# SFP__Connectors.net
KiCad netlist of a schematic drawn in Altium Designer
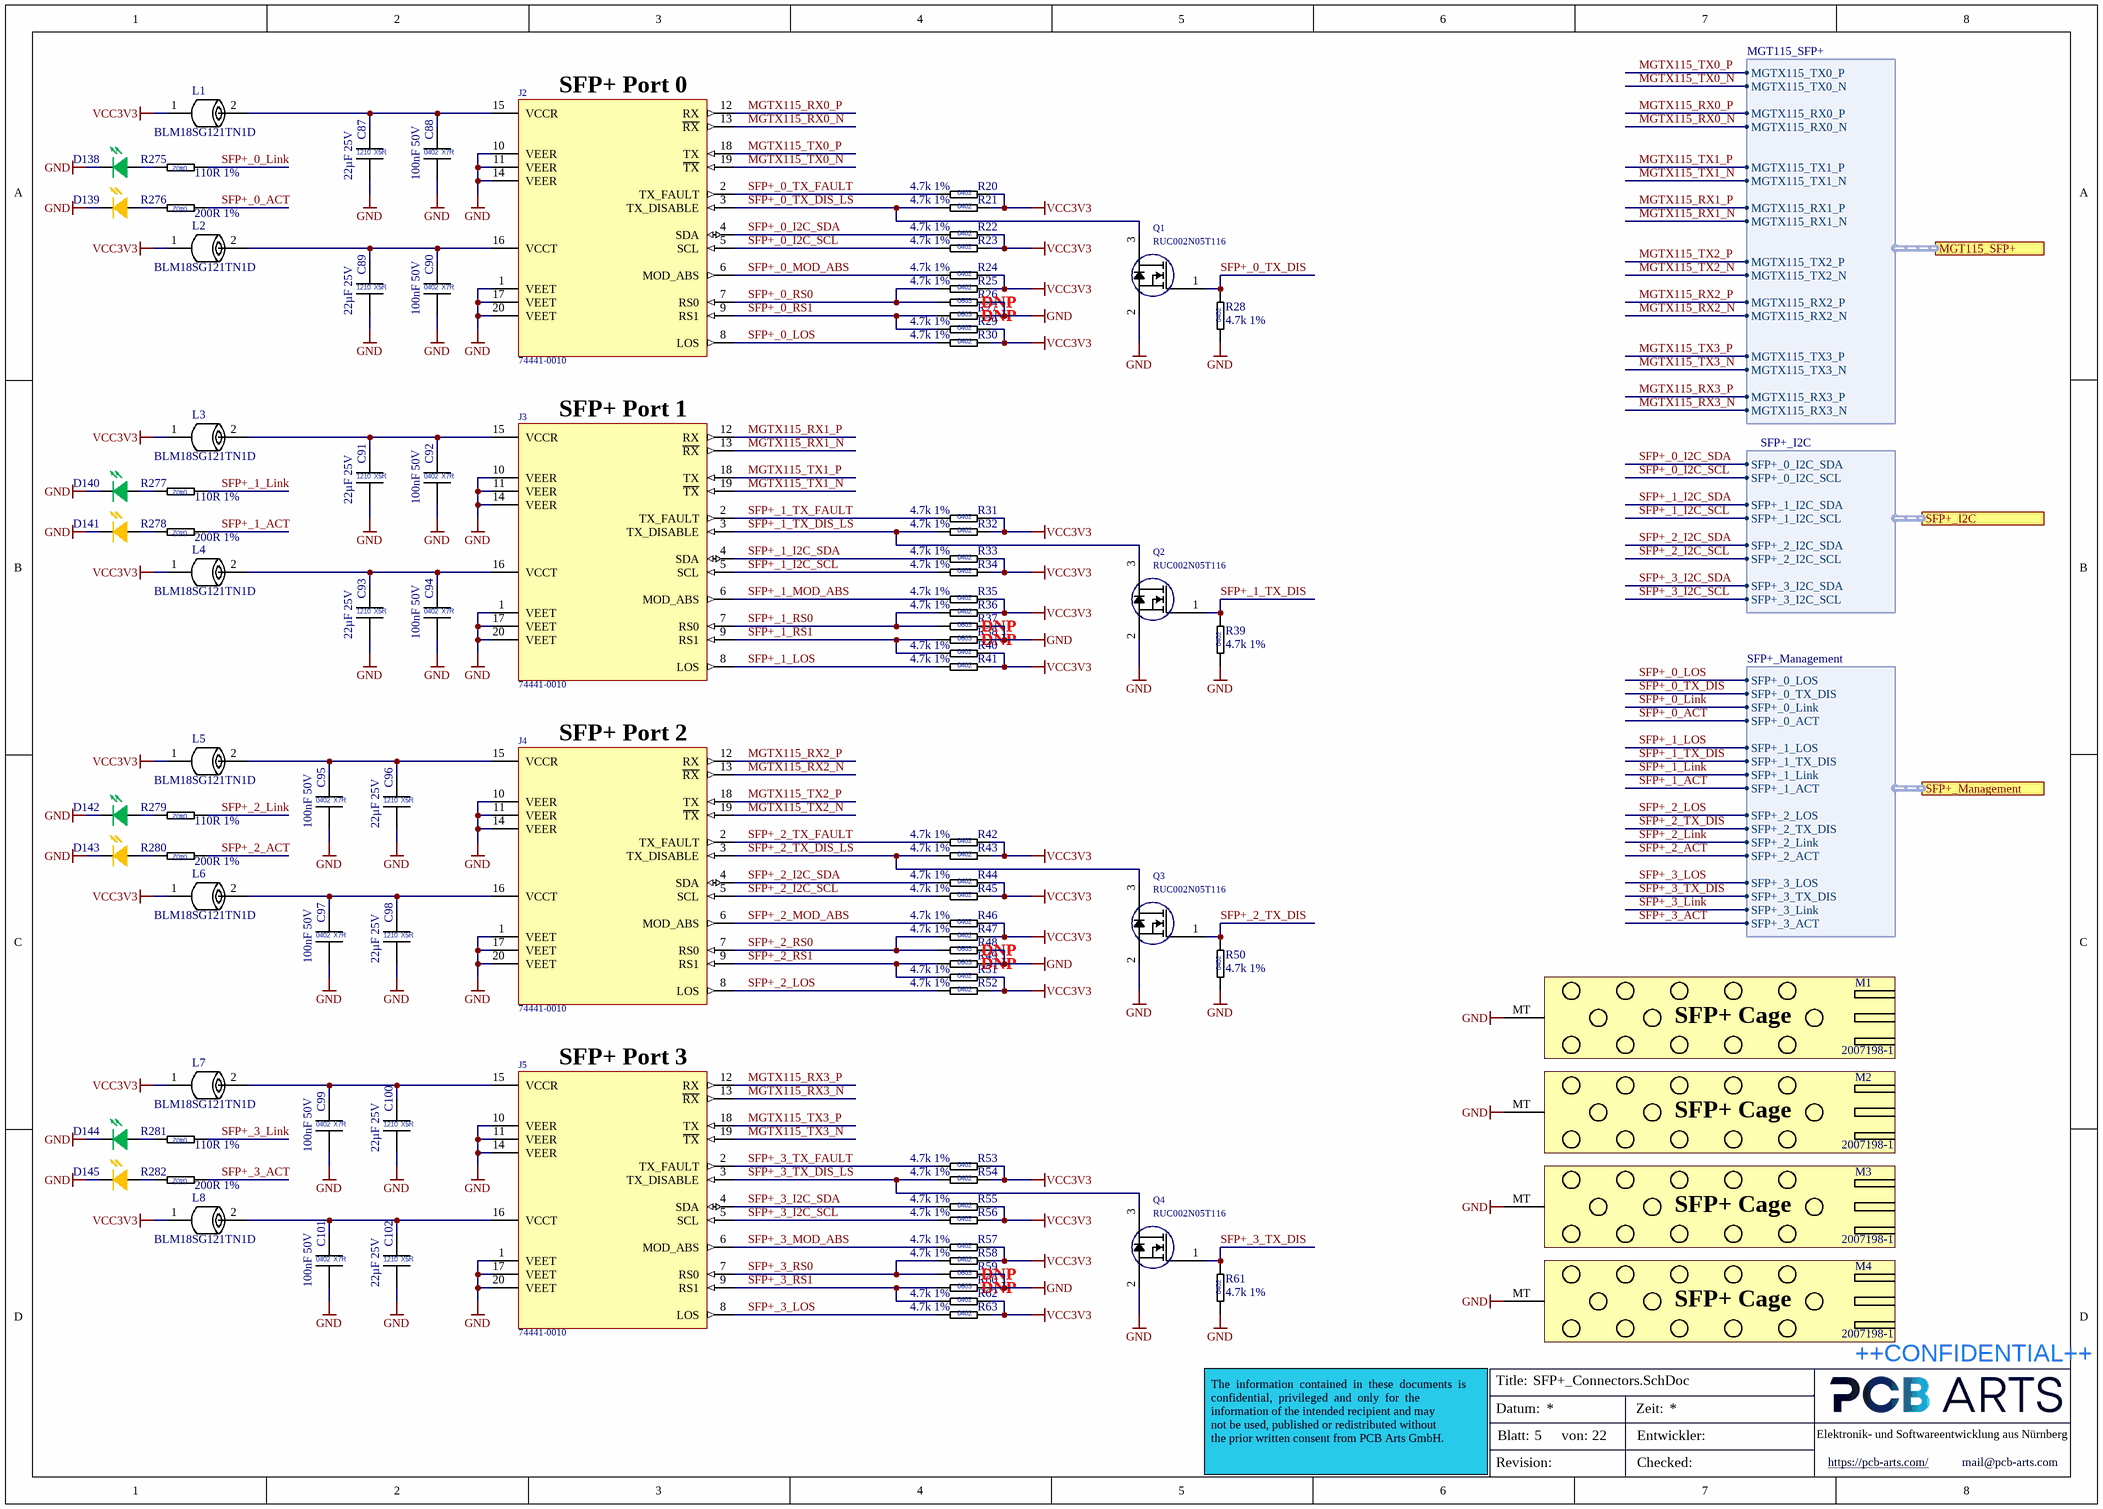
[diagram p0: SFP+_Connectors.SchDoc]

(export (version "E")
  (design (tool "Eeschema 10.0.6"))
  (components
    (comp (ref "C87")
      (value "22µF 25V")
      (footprint "Cap:CAP_1210")
      (description "Multilayer Ceramic Capacitors MLCC - SMD/SMT 1210 25VDC")
      (libsource (lib "Cap") (part "CAP_1210_22µF_25V"))
    )
    (comp (ref "C88")
      (value "100nF 50V")
      (footprint "Cap:CAP_0402_L")
      (description "Multilayer Ceramic Capacitors MLCC - SMD/SMT 0402 50VDC")
      (libsource (lib "Cap") (part "CAP_0402_100nF_50V"))
    )
    (comp (ref "C89")
      (value "22µF 25V")
      (footprint "Cap:CAP_1210")
      (description "Multilayer Ceramic Capacitors MLCC - SMD/SMT 1210 25VDC")
      (libsource (lib "Cap") (part "CAP_1210_22µF_25V"))
    )
    (comp (ref "C90")
      (value "100nF 50V")
      (footprint "Cap:CAP_0402_L")
      (description "Multilayer Ceramic Capacitors MLCC - SMD/SMT 0402 50VDC")
      (libsource (lib "Cap") (part "CAP_0402_100nF_50V"))
    )
    (comp (ref "C91")
      (value "22µF 25V")
      (footprint "Cap:CAP_1210")
      (description "Multilayer Ceramic Capacitors MLCC - SMD/SMT 1210 25VDC")
      (libsource (lib "Cap") (part "CAP_1210_22µF_25V"))
    )
    (comp (ref "C92")
      (value "100nF 50V")
      (footprint "Cap:CAP_0402_L")
      (description "Multilayer Ceramic Capacitors MLCC - SMD/SMT 0402 50VDC")
      (libsource (lib "Cap") (part "CAP_0402_100nF_50V"))
    )
    (comp (ref "C93")
      (value "22µF 25V")
      (footprint "Cap:CAP_1210")
      (description "Multilayer Ceramic Capacitors MLCC - SMD/SMT 1210 25VDC")
      (libsource (lib "Cap") (part "CAP_1210_22µF_25V"))
    )
    (comp (ref "C94")
      (value "100nF 50V")
      (footprint "Cap:CAP_0402_L")
      (description "Multilayer Ceramic Capacitors MLCC - SMD/SMT 0402 50VDC")
      (libsource (lib "Cap") (part "CAP_0402_100nF_50V"))
    )
    (comp (ref "C95")
      (value "100nF 50V")
      (footprint "Cap:CAP_0402_L")
      (description "Multilayer Ceramic Capacitors MLCC - SMD/SMT 0402 50VDC")
      (libsource (lib "Cap") (part "CAP_0402_100nF_50V"))
    )
    (comp (ref "C96")
      (value "22µF 25V")
      (footprint "Cap:CAP_1210")
      (description "Multilayer Ceramic Capacitors MLCC - SMD/SMT 1210 25VDC")
      (libsource (lib "Cap") (part "CAP_1210_22µF_25V"))
    )
    (comp (ref "C97")
      (value "100nF 50V")
      (footprint "Cap:CAP_0402_L")
      (description "Multilayer Ceramic Capacitors MLCC - SMD/SMT 0402 50VDC")
      (libsource (lib "Cap") (part "CAP_0402_100nF_50V"))
    )
    (comp (ref "C98")
      (value "22µF 25V")
      (footprint "Cap:CAP_1210")
      (description "Multilayer Ceramic Capacitors MLCC - SMD/SMT 1210 25VDC")
      (libsource (lib "Cap") (part "CAP_1210_22µF_25V"))
    )
    (comp (ref "C99")
      (value "100nF 50V")
      (footprint "Cap:CAP_0402_L")
      (description "Multilayer Ceramic Capacitors MLCC - SMD/SMT 0402 50VDC")
      (libsource (lib "Cap") (part "CAP_0402_100nF_50V"))
    )
    (comp (ref "C100")
      (value "22µF 25V")
      (footprint "Cap:CAP_1210")
      (description "Multilayer Ceramic Capacitors MLCC - SMD/SMT 1210 25VDC")
      (libsource (lib "Cap") (part "CAP_1210_22µF_25V"))
    )
    (comp (ref "C101")
      (value "100nF 50V")
      (footprint "Cap:CAP_0402_L")
      (description "Multilayer Ceramic Capacitors MLCC - SMD/SMT 0402 50VDC")
      (libsource (lib "Cap") (part "CAP_0402_100nF_50V"))
    )
    (comp (ref "C102")
      (value "22µF 25V")
      (footprint "Cap:CAP_1210")
      (description "Multilayer Ceramic Capacitors MLCC - SMD/SMT 1210 25VDC")
      (libsource (lib "Cap") (part "CAP_1210_22µF_25V"))
    )
    (comp (ref "D138")
      (value "LTST-S270KGKT")
      (footprint "Active:LED-0603 Sideview")
      (description "GREEN  0603 Light Emitting Diode")
      (libsource (lib "Active") (part "LED 0603 Green Sideview"))
    )
    (comp (ref "D139")
      (value "LTST-S270KFKT")
      (footprint "Active:LED-0603 Sideview")
      (description "ORANGE 0603 Light Emitting Diode")
      (libsource (lib "Active") (part "LED 0603 ORANGE Sideview"))
    )
    (comp (ref "D140")
      (value "LTST-S270KGKT")
      (footprint "Active:LED-0603 Sideview")
      (description "GREEN  0603 Light Emitting Diode")
      (libsource (lib "Active") (part "LED 0603 Green Sideview"))
    )
    (comp (ref "D141")
      (value "LTST-S270KFKT")
      (footprint "Active:LED-0603 Sideview")
      (description "ORANGE 0603 Light Emitting Diode")
      (libsource (lib "Active") (part "LED 0603 ORANGE Sideview"))
    )
    (comp (ref "D142")
      (value "LTST-S270KGKT")
      (footprint "Active:LED-0603 Sideview")
      (description "GREEN  0603 Light Emitting Diode")
      (libsource (lib "Active") (part "LED 0603 Green Sideview"))
    )
    (comp (ref "D143")
      (value "LTST-S270KFKT")
      (footprint "Active:LED-0603 Sideview")
      (description "ORANGE 0603 Light Emitting Diode")
      (libsource (lib "Active") (part "LED 0603 ORANGE Sideview"))
    )
    (comp (ref "D144")
      (value "LTST-S270KGKT")
      (footprint "Active:LED-0603 Sideview")
      (description "GREEN  0603 Light Emitting Diode")
      (libsource (lib "Active") (part "LED 0603 Green Sideview"))
    )
    (comp (ref "D145")
      (value "LTST-S270KFKT")
      (footprint "Active:LED-0603 Sideview")
      (description "ORANGE 0603 Light Emitting Diode")
      (libsource (lib "Active") (part "LED 0603 ORANGE Sideview"))
    )
    (comp (ref "J2")
      (value "74441-0010")
      (footprint "Conn:74441-0010")
      (description "20 Pin Right Angle 0.8mm SMD Card Edge Connector for SFP+")
      (libsource (lib "Conn") (part "74441-0010_Card Edge Connector for SFP+"))
    )
    (comp (ref "J3")
      (value "74441-0010")
      (footprint "Conn:74441-0010")
      (description "20 Pin Right Angle 0.8mm SMD Card Edge Connector for SFP+")
      (libsource (lib "Conn") (part "74441-0010_Card Edge Connector for SFP+"))
    )
    (comp (ref "J4")
      (value "74441-0010")
      (footprint "Conn:74441-0010")
      (description "20 Pin Right Angle 0.8mm SMD Card Edge Connector for SFP+")
      (libsource (lib "Conn") (part "74441-0010_Card Edge Connector for SFP+"))
    )
    (comp (ref "J5")
      (value "74441-0010")
      (footprint "Conn:74441-0010")
      (description "20 Pin Right Angle 0.8mm SMD Card Edge Connector for SFP+")
      (libsource (lib "Conn") (part "74441-0010_Card Edge Connector for SFP+"))
    )
    (comp (ref "L1")
      (value "BLM18SG121TN1D")
      (footprint "Indc:L_0603")
      (description "Ferritperlen BLM18_xN 0603 100MHz 120Ohm 3000mA 25mOhm RSER")
      (libsource (lib "Indc") (part "BLM18SG121TN1D_Ferrite Beads 0603 120Ohms 3000mA"))
    )
    (comp (ref "L2")
      (value "BLM18SG121TN1D")
      (footprint "Indc:L_0603")
      (description "Ferritperlen BLM18_xN 0603 100MHz 120Ohm 3000mA 25mOhm RSER")
      (libsource (lib "Indc") (part "BLM18SG121TN1D_Ferrite Beads 0603 120Ohms 3000mA"))
    )
    (comp (ref "L3")
      (value "BLM18SG121TN1D")
      (footprint "Indc:L_0603")
      (description "Ferritperlen BLM18_xN 0603 100MHz 120Ohm 3000mA 25mOhm RSER")
      (libsource (lib "Indc") (part "BLM18SG121TN1D_Ferrite Beads 0603 120Ohms 3000mA"))
    )
    (comp (ref "L4")
      (value "BLM18SG121TN1D")
      (footprint "Indc:L_0603")
      (description "Ferritperlen BLM18_xN 0603 100MHz 120Ohm 3000mA 25mOhm RSER")
      (libsource (lib "Indc") (part "BLM18SG121TN1D_Ferrite Beads 0603 120Ohms 3000mA"))
    )
    (comp (ref "L5")
      (value "BLM18SG121TN1D")
      (footprint "Indc:L_0603")
      (description "Ferritperlen BLM18_xN 0603 100MHz 120Ohm 3000mA 25mOhm RSER")
      (libsource (lib "Indc") (part "BLM18SG121TN1D_Ferrite Beads 0603 120Ohms 3000mA"))
    )
    (comp (ref "L6")
      (value "BLM18SG121TN1D")
      (footprint "Indc:L_0603")
      (description "Ferritperlen BLM18_xN 0603 100MHz 120Ohm 3000mA 25mOhm RSER")
      (libsource (lib "Indc") (part "BLM18SG121TN1D_Ferrite Beads 0603 120Ohms 3000mA"))
    )
    (comp (ref "L7")
      (value "BLM18SG121TN1D")
      (footprint "Indc:L_0603")
      (description "Ferritperlen BLM18_xN 0603 100MHz 120Ohm 3000mA 25mOhm RSER")
      (libsource (lib "Indc") (part "BLM18SG121TN1D_Ferrite Beads 0603 120Ohms 3000mA"))
    )
    (comp (ref "L8")
      (value "BLM18SG121TN1D")
      (footprint "Indc:L_0603")
      (description "Ferritperlen BLM18_xN 0603 100MHz 120Ohm 3000mA 25mOhm RSER")
      (libsource (lib "Indc") (part "BLM18SG121TN1D_Ferrite Beads 0603 120Ohms 3000mA"))
    )
    (comp (ref "M1")
      (value "2007198-1")
      (footprint "Conn:2007198-1")
      (description "2SFP+ Cage, 1x1, external EMV springs, no lightpipes")
      (libsource (lib "Conn") (part "2007198-1_2SFP+ Cage, 1x1, external EMV springs, no lightpipes"))
    )
    (comp (ref "M2")
      (value "2007198-1")
      (footprint "Conn:2007198-1")
      (description "2SFP+ Cage, 1x1, external EMV springs, no lightpipes")
      (libsource (lib "Conn") (part "2007198-1_2SFP+ Cage, 1x1, external EMV springs, no lightpipes"))
    )
    (comp (ref "M3")
      (value "2007198-1")
      (footprint "Conn:2007198-1")
      (description "2SFP+ Cage, 1x1, external EMV springs, no lightpipes")
      (libsource (lib "Conn") (part "2007198-1_2SFP+ Cage, 1x1, external EMV springs, no lightpipes"))
    )
    (comp (ref "M4")
      (value "2007198-1")
      (footprint "Conn:2007198-1")
      (description "2SFP+ Cage, 1x1, external EMV springs, no lightpipes")
      (libsource (lib "Conn") (part "2007198-1_2SFP+ Cage, 1x1, external EMV springs, no lightpipes"))
    )
    (comp (ref "Q1")
      (value "RUC002N05T116")
      (footprint "trans:SOT95P251X112-3N")
      (description "MOSFET N-Ch 1.2 VGS Spec")
      (libsource (lib "Trans") (part "RUC002N05T116_MOSFET N-Ch 1.2 VGS Spec"))
    )
    (comp (ref "Q2")
      (value "RUC002N05T116")
      (footprint "trans:SOT95P251X112-3N")
      (description "MOSFET N-Ch 1.2 VGS Spec")
      (libsource (lib "Trans") (part "RUC002N05T116_MOSFET N-Ch 1.2 VGS Spec"))
    )
    (comp (ref "Q3")
      (value "RUC002N05T116")
      (footprint "trans:SOT95P251X112-3N")
      (description "MOSFET N-Ch 1.2 VGS Spec")
      (libsource (lib "Trans") (part "RUC002N05T116_MOSFET N-Ch 1.2 VGS Spec"))
    )
    (comp (ref "Q4")
      (value "RUC002N05T116")
      (footprint "trans:SOT95P251X112-3N")
      (description "MOSFET N-Ch 1.2 VGS Spec")
      (libsource (lib "Trans") (part "RUC002N05T116_MOSFET N-Ch 1.2 VGS Spec"))
    )
    (comp (ref "R20")
      (value "4.7k 1%")
      (footprint "Res:RES_0402_L")
      (description "Thick Film Resistors - SMD 4.7kOhm 1%")
      (libsource (lib "Res") (part "RES_0402_4.7k_1%"))
    )
    (comp (ref "R21")
      (value "4.7k 1%")
      (footprint "Res:RES_0402_L")
      (description "Thick Film Resistors - SMD 4.7kOhm 1%")
      (libsource (lib "Res") (part "RES_0402_4.7k_1%"))
    )
    (comp (ref "R22")
      (value "4.7k 1%")
      (footprint "Res:RES_0402_L")
      (description "Thick Film Resistors - SMD 4.7kOhm 1%")
      (libsource (lib "Res") (part "RES_0402_4.7k_1%"))
    )
    (comp (ref "R23")
      (value "4.7k 1%")
      (footprint "Res:RES_0402_L")
      (description "Thick Film Resistors - SMD 4.7kOhm 1%")
      (libsource (lib "Res") (part "RES_0402_4.7k_1%"))
    )
    (comp (ref "R24")
      (value "4.7k 1%")
      (footprint "Res:RES_0402_L")
      (description "Thick Film Resistors - SMD 4.7kOhm 1%")
      (libsource (lib "Res") (part "RES_0402_4.7k_1%"))
    )
    (comp (ref "R25")
      (value "4.7k 1%")
      (footprint "Res:RES_0402_L")
      (description "Thick Film Resistors - SMD 4.7kOhm 1%")
      (libsource (lib "Res") (part "RES_0402_4.7k_1%"))
    )
    (comp (ref "R26")
      (value "0R Jumper")
      (footprint "Res:RES_0603_L")
      (description "Thick Film Resistors - SMD 0Ohm Jumper")
      (libsource (lib "Res") (part "RES_0603_0R_Jumper"))
    )
    (comp (ref "R27")
      (value "0R Jumper")
      (footprint "Res:RES_0603_L")
      (description "Thick Film Resistors - SMD 0Ohm Jumper")
      (libsource (lib "Res") (part "RES_0603_0R_Jumper"))
    )
    (comp (ref "R28")
      (value "4.7k 1%")
      (footprint "Res:RES_0402_L")
      (description "Thick Film Resistors - SMD 4.7kOhm 1%")
      (libsource (lib "Res") (part "RES_0402_4.7k_1%"))
    )
    (comp (ref "R29")
      (value "4.7k 1%")
      (footprint "Res:RES_0402_L")
      (description "Thick Film Resistors - SMD 4.7kOhm 1%")
      (libsource (lib "Res") (part "RES_0402_4.7k_1%"))
    )
    (comp (ref "R30")
      (value "4.7k 1%")
      (footprint "Res:RES_0402_L")
      (description "Thick Film Resistors - SMD 4.7kOhm 1%")
      (libsource (lib "Res") (part "RES_0402_4.7k_1%"))
    )
    (comp (ref "R31")
      (value "4.7k 1%")
      (footprint "Res:RES_0402_L")
      (description "Thick Film Resistors - SMD 4.7kOhm 1%")
      (libsource (lib "Res") (part "RES_0402_4.7k_1%"))
    )
    (comp (ref "R32")
      (value "4.7k 1%")
      (footprint "Res:RES_0402_L")
      (description "Thick Film Resistors - SMD 4.7kOhm 1%")
      (libsource (lib "Res") (part "RES_0402_4.7k_1%"))
    )
    (comp (ref "R33")
      (value "4.7k 1%")
      (footprint "Res:RES_0402_L")
      (description "Thick Film Resistors - SMD 4.7kOhm 1%")
      (libsource (lib "Res") (part "RES_0402_4.7k_1%"))
    )
    (comp (ref "R34")
      (value "4.7k 1%")
      (footprint "Res:RES_0402_L")
      (description "Thick Film Resistors - SMD 4.7kOhm 1%")
      (libsource (lib "Res") (part "RES_0402_4.7k_1%"))
    )
    (comp (ref "R35")
      (value "4.7k 1%")
      (footprint "Res:RES_0402_L")
      (description "Thick Film Resistors - SMD 4.7kOhm 1%")
      (libsource (lib "Res") (part "RES_0402_4.7k_1%"))
    )
    (comp (ref "R36")
      (value "4.7k 1%")
      (footprint "Res:RES_0402_L")
      (description "Thick Film Resistors - SMD 4.7kOhm 1%")
      (libsource (lib "Res") (part "RES_0402_4.7k_1%"))
    )
    (comp (ref "R37")
      (value "0R Jumper")
      (footprint "Res:RES_0603_L")
      (description "Thick Film Resistors - SMD 0Ohm Jumper")
      (libsource (lib "Res") (part "RES_0603_0R_Jumper"))
    )
    (comp (ref "R38")
      (value "0R Jumper")
      (footprint "Res:RES_0603_L")
      (description "Thick Film Resistors - SMD 0Ohm Jumper")
      (libsource (lib "Res") (part "RES_0603_0R_Jumper"))
    )
    (comp (ref "R39")
      (value "4.7k 1%")
      (footprint "Res:RES_0402_L")
      (description "Thick Film Resistors - SMD 4.7kOhm 1%")
      (libsource (lib "Res") (part "RES_0402_4.7k_1%"))
    )
    (comp (ref "R40")
      (value "4.7k 1%")
      (footprint "Res:RES_0402_L")
      (description "Thick Film Resistors - SMD 4.7kOhm 1%")
      (libsource (lib "Res") (part "RES_0402_4.7k_1%"))
    )
    (comp (ref "R41")
      (value "4.7k 1%")
      (footprint "Res:RES_0402_L")
      (description "Thick Film Resistors - SMD 4.7kOhm 1%")
      (libsource (lib "Res") (part "RES_0402_4.7k_1%"))
    )
    (comp (ref "R42")
      (value "4.7k 1%")
      (footprint "Res:RES_0402_L")
      (description "Thick Film Resistors - SMD 4.7kOhm 1%")
      (libsource (lib "Res") (part "RES_0402_4.7k_1%"))
    )
    (comp (ref "R43")
      (value "4.7k 1%")
      (footprint "Res:RES_0402_L")
      (description "Thick Film Resistors - SMD 4.7kOhm 1%")
      (libsource (lib "Res") (part "RES_0402_4.7k_1%"))
    )
    (comp (ref "R44")
      (value "4.7k 1%")
      (footprint "Res:RES_0402_L")
      (description "Thick Film Resistors - SMD 4.7kOhm 1%")
      (libsource (lib "Res") (part "RES_0402_4.7k_1%"))
    )
    (comp (ref "R45")
      (value "4.7k 1%")
      (footprint "Res:RES_0402_L")
      (description "Thick Film Resistors - SMD 4.7kOhm 1%")
      (libsource (lib "Res") (part "RES_0402_4.7k_1%"))
    )
    (comp (ref "R46")
      (value "4.7k 1%")
      (footprint "Res:RES_0402_L")
      (description "Thick Film Resistors - SMD 4.7kOhm 1%")
      (libsource (lib "Res") (part "RES_0402_4.7k_1%"))
    )
    (comp (ref "R47")
      (value "4.7k 1%")
      (footprint "Res:RES_0402_L")
      (description "Thick Film Resistors - SMD 4.7kOhm 1%")
      (libsource (lib "Res") (part "RES_0402_4.7k_1%"))
    )
    (comp (ref "R48")
      (value "0R Jumper")
      (footprint "Res:RES_0603_L")
      (description "Thick Film Resistors - SMD 0Ohm Jumper")
      (libsource (lib "Res") (part "RES_0603_0R_Jumper"))
    )
    (comp (ref "R49")
      (value "0R Jumper")
      (footprint "Res:RES_0603_L")
      (description "Thick Film Resistors - SMD 0Ohm Jumper")
      (libsource (lib "Res") (part "RES_0603_0R_Jumper"))
    )
    (comp (ref "R50")
      (value "4.7k 1%")
      (footprint "Res:RES_0402_L")
      (description "Thick Film Resistors - SMD 4.7kOhm 1%")
      (libsource (lib "Res") (part "RES_0402_4.7k_1%"))
    )
    (comp (ref "R51")
      (value "4.7k 1%")
      (footprint "Res:RES_0402_L")
      (description "Thick Film Resistors - SMD 4.7kOhm 1%")
      (libsource (lib "Res") (part "RES_0402_4.7k_1%"))
    )
    (comp (ref "R52")
      (value "4.7k 1%")
      (footprint "Res:RES_0402_L")
      (description "Thick Film Resistors - SMD 4.7kOhm 1%")
      (libsource (lib "Res") (part "RES_0402_4.7k_1%"))
    )
    (comp (ref "R53")
      (value "4.7k 1%")
      (footprint "Res:RES_0402_L")
      (description "Thick Film Resistors - SMD 4.7kOhm 1%")
      (libsource (lib "Res") (part "RES_0402_4.7k_1%"))
    )
    (comp (ref "R54")
      (value "4.7k 1%")
      (footprint "Res:RES_0402_L")
      (description "Thick Film Resistors - SMD 4.7kOhm 1%")
      (libsource (lib "Res") (part "RES_0402_4.7k_1%"))
    )
    (comp (ref "R55")
      (value "4.7k 1%")
      (footprint "Res:RES_0402_L")
      (description "Thick Film Resistors - SMD 4.7kOhm 1%")
      (libsource (lib "Res") (part "RES_0402_4.7k_1%"))
    )
    (comp (ref "R56")
      (value "4.7k 1%")
      (footprint "Res:RES_0402_L")
      (description "Thick Film Resistors - SMD 4.7kOhm 1%")
      (libsource (lib "Res") (part "RES_0402_4.7k_1%"))
    )
    (comp (ref "R57")
      (value "4.7k 1%")
      (footprint "Res:RES_0402_L")
      (description "Thick Film Resistors - SMD 4.7kOhm 1%")
      (libsource (lib "Res") (part "RES_0402_4.7k_1%"))
    )
    (comp (ref "R58")
      (value "4.7k 1%")
      (footprint "Res:RES_0402_L")
      (description "Thick Film Resistors - SMD 4.7kOhm 1%")
      (libsource (lib "Res") (part "RES_0402_4.7k_1%"))
    )
    (comp (ref "R59")
      (value "0R Jumper")
      (footprint "Res:RES_0603_L")
      (description "Thick Film Resistors - SMD 0Ohm Jumper")
      (libsource (lib "Res") (part "RES_0603_0R_Jumper"))
    )
    (comp (ref "R60")
      (value "0R Jumper")
      (footprint "Res:RES_0603_L")
      (description "Thick Film Resistors - SMD 0Ohm Jumper")
      (libsource (lib "Res") (part "RES_0603_0R_Jumper"))
    )
    (comp (ref "R61")
      (value "4.7k 1%")
      (footprint "Res:RES_0402_L")
      (description "Thick Film Resistors - SMD 4.7kOhm 1%")
      (libsource (lib "Res") (part "RES_0402_4.7k_1%"))
    )
    (comp (ref "R62")
      (value "4.7k 1%")
      (footprint "Res:RES_0402_L")
      (description "Thick Film Resistors - SMD 4.7kOhm 1%")
      (libsource (lib "Res") (part "RES_0402_4.7k_1%"))
    )
    (comp (ref "R63")
      (value "4.7k 1%")
      (footprint "Res:RES_0402_L")
      (description "Thick Film Resistors - SMD 4.7kOhm 1%")
      (libsource (lib "Res") (part "RES_0402_4.7k_1%"))
    )
    (comp (ref "R275")
      (value "110R 1%")
      (footprint "Res:RES_0402_L")
      (description "Thick Film Resistors - SMD 110Ohm 1%")
      (libsource (lib "Res") (part "RES_0402_110R_1%"))
    )
    (comp (ref "R276")
      (value "200R 1%")
      (footprint "Res:RES_0402_L")
      (description "Thick Film Resistors - SMD 200Ohm 1%")
      (libsource (lib "Res") (part "RES_0402_200R 1%"))
    )
    (comp (ref "R277")
      (value "110R 1%")
      (footprint "Res:RES_0402_L")
      (description "Thick Film Resistors - SMD 110Ohm 1%")
      (libsource (lib "Res") (part "RES_0402_110R_1%"))
    )
    (comp (ref "R278")
      (value "200R 1%")
      (footprint "Res:RES_0402_L")
      (description "Thick Film Resistors - SMD 200Ohm 1%")
      (libsource (lib "Res") (part "RES_0402_200R 1%"))
    )
    (comp (ref "R279")
      (value "110R 1%")
      (footprint "Res:RES_0402_L")
      (description "Thick Film Resistors - SMD 110Ohm 1%")
      (libsource (lib "Res") (part "RES_0402_110R_1%"))
    )
    (comp (ref "R280")
      (value "200R 1%")
      (footprint "Res:RES_0402_L")
      (description "Thick Film Resistors - SMD 200Ohm 1%")
      (libsource (lib "Res") (part "RES_0402_200R 1%"))
    )
    (comp (ref "R281")
      (value "110R 1%")
      (footprint "Res:RES_0402_L")
      (description "Thick Film Resistors - SMD 110Ohm 1%")
      (libsource (lib "Res") (part "RES_0402_110R_1%"))
    )
    (comp (ref "R282")
      (value "200R 1%")
      (footprint "Res:RES_0402_L")
      (description "Thick Film Resistors - SMD 200Ohm 1%")
      (libsource (lib "Res") (part "RES_0402_200R 1%"))
    )
  )
  (nets
    (net (code "4") (name "/MGTX115_RX0_N") (class "Default")
      (node (ref "J2") (pin "13") (pinfunction "~{RX}_13") (pintype "output"))
    )
    (net (code "5") (name "/MGTX115_RX0_P") (class "Default")
      (node (ref "J2") (pin "12") (pinfunction "RX_12") (pintype "output"))
    )
    (net (code "6") (name "/MGTX115_RX1_N") (class "Default")
      (node (ref "J3") (pin "13") (pinfunction "~{RX}_13") (pintype "output"))
    )
    (net (code "7") (name "/MGTX115_RX1_P") (class "Default")
      (node (ref "J3") (pin "12") (pinfunction "RX_12") (pintype "output"))
    )
    (net (code "8") (name "/MGTX115_RX2_N") (class "Default")
      (node (ref "J4") (pin "13") (pinfunction "~{RX}_13") (pintype "output"))
    )
    (net (code "9") (name "/MGTX115_RX2_P") (class "Default")
      (node (ref "J4") (pin "12") (pinfunction "RX_12") (pintype "output"))
    )
    (net (code "10") (name "/MGTX115_RX3_N") (class "Default")
      (node (ref "J5") (pin "13") (pinfunction "~{RX}_13") (pintype "output"))
    )
    (net (code "11") (name "/MGTX115_RX3_P") (class "Default")
      (node (ref "J5") (pin "12") (pinfunction "RX_12") (pintype "output"))
    )
    (net (code "12") (name "/MGTX115_TX0_N") (class "Default")
      (node (ref "J2") (pin "19") (pinfunction "~{TX}_19") (pintype "input"))
    )
    (net (code "13") (name "/MGTX115_TX0_P") (class "Default")
      (node (ref "J2") (pin "18") (pinfunction "TX_18") (pintype "input"))
    )
    (net (code "14") (name "/MGTX115_TX1_N") (class "Default")
      (node (ref "J3") (pin "19") (pinfunction "~{TX}_19") (pintype "input"))
    )
    (net (code "15") (name "/MGTX115_TX1_P") (class "Default")
      (node (ref "J3") (pin "18") (pinfunction "TX_18") (pintype "input"))
    )
    (net (code "16") (name "/MGTX115_TX2_N") (class "Default")
      (node (ref "J4") (pin "19") (pinfunction "~{TX}_19") (pintype "input"))
    )
    (net (code "17") (name "/MGTX115_TX2_P") (class "Default")
      (node (ref "J4") (pin "18") (pinfunction "TX_18") (pintype "input"))
    )
    (net (code "18") (name "/MGTX115_TX3_N") (class "Default")
      (node (ref "J5") (pin "19") (pinfunction "~{TX}_19") (pintype "input"))
    )
    (net (code "19") (name "/MGTX115_TX3_P") (class "Default")
      (node (ref "J5") (pin "18") (pinfunction "TX_18") (pintype "input"))
    )
    (net (code "20") (name "/SFP+_0_ACT") (class "Default")
      (node (ref "R276") (pin "1") (pinfunction "1_1") (pintype "passive"))
    )
    (net (code "21") (name "/SFP+_0_I2C_SCL") (class "Default")
      (node (ref "J2") (pin "5") (pinfunction "SCL_5") (pintype "input"))
      (node (ref "R23") (pin "1") (pinfunction "1_1") (pintype "passive"))
    )
    (net (code "22") (name "/SFP+_0_I2C_SDA") (class "Default")
      (node (ref "J2") (pin "4") (pinfunction "SDA_4") (pintype "bidirectional"))
      (node (ref "R22") (pin "1") (pinfunction "1_1") (pintype "passive"))
    )
    (net (code "23") (name "/SFP+_0_LOS") (class "Default")
      (node (ref "J2") (pin "8") (pinfunction "LOS_8") (pintype "output"))
      (node (ref "R30") (pin "1") (pinfunction "1_1") (pintype "passive"))
    )
    (net (code "24") (name "/SFP+_0_Link") (class "Default")
      (node (ref "R275") (pin "1") (pinfunction "1_1") (pintype "passive"))
    )
    (net (code "25") (name "/SFP+_0_MOD_ABS") (class "Default")
      (node (ref "J2") (pin "6") (pinfunction "MOD_ABS_6") (pintype "output"))
      (node (ref "R24") (pin "1") (pinfunction "1_1") (pintype "passive"))
    )
    (net (code "26") (name "/SFP+_0_RS0") (class "Default")
      (node (ref "J2") (pin "7") (pinfunction "RS0_7") (pintype "input"))
      (node (ref "R25") (pin "1") (pinfunction "1_1") (pintype "passive"))
      (node (ref "R26") (pin "1") (pinfunction "1_1") (pintype "passive"))
    )
    (net (code "27") (name "/SFP+_0_RS1") (class "Default")
      (node (ref "J2") (pin "9") (pinfunction "RS1_9") (pintype "input"))
      (node (ref "R27") (pin "1") (pinfunction "1_1") (pintype "passive"))
      (node (ref "R29") (pin "1") (pinfunction "1_1") (pintype "passive"))
    )
    (net (code "28") (name "/SFP+_0_TX_DIS") (class "Default")
      (node (ref "Q1") (pin "1") (pinfunction "G_1") (pintype "passive"))
      (node (ref "R28") (pin "2") (pinfunction "2_2") (pintype "passive"))
    )
    (net (code "29") (name "/SFP+_0_TX_DIS_LS") (class "Default")
      (node (ref "J2") (pin "3") (pinfunction "TX_DISABLE_3") (pintype "input"))
      (node (ref "Q1") (pin "3") (pinfunction "S_3") (pintype "passive"))
      (node (ref "R21") (pin "1") (pinfunction "1_1") (pintype "passive"))
    )
    (net (code "30") (name "/SFP+_0_TX_FAULT") (class "Default")
      (node (ref "J2") (pin "2") (pinfunction "TX_FAULT_2") (pintype "output"))
      (node (ref "R20") (pin "1") (pinfunction "1_1") (pintype "passive"))
    )
    (net (code "31") (name "/SFP+_1_ACT") (class "Default")
      (node (ref "R278") (pin "1") (pinfunction "1_1") (pintype "passive"))
    )
    (net (code "32") (name "/SFP+_1_I2C_SCL") (class "Default")
      (node (ref "J3") (pin "5") (pinfunction "SCL_5") (pintype "input"))
      (node (ref "R34") (pin "1") (pinfunction "1_1") (pintype "passive"))
    )
    (net (code "33") (name "/SFP+_1_I2C_SDA") (class "Default")
      (node (ref "J3") (pin "4") (pinfunction "SDA_4") (pintype "bidirectional"))
      (node (ref "R33") (pin "1") (pinfunction "1_1") (pintype "passive"))
    )
    (net (code "34") (name "/SFP+_1_LOS") (class "Default")
      (node (ref "J3") (pin "8") (pinfunction "LOS_8") (pintype "output"))
      (node (ref "R41") (pin "1") (pinfunction "1_1") (pintype "passive"))
    )
    (net (code "35") (name "/SFP+_1_Link") (class "Default")
      (node (ref "R277") (pin "1") (pinfunction "1_1") (pintype "passive"))
    )
    (net (code "36") (name "/SFP+_1_MOD_ABS") (class "Default")
      (node (ref "J3") (pin "6") (pinfunction "MOD_ABS_6") (pintype "output"))
      (node (ref "R35") (pin "1") (pinfunction "1_1") (pintype "passive"))
    )
    (net (code "37") (name "/SFP+_1_RS0") (class "Default")
      (node (ref "J3") (pin "7") (pinfunction "RS0_7") (pintype "input"))
      (node (ref "R36") (pin "1") (pinfunction "1_1") (pintype "passive"))
      (node (ref "R37") (pin "1") (pinfunction "1_1") (pintype "passive"))
    )
    (net (code "38") (name "/SFP+_1_RS1") (class "Default")
      (node (ref "J3") (pin "9") (pinfunction "RS1_9") (pintype "input"))
      (node (ref "R38") (pin "1") (pinfunction "1_1") (pintype "passive"))
      (node (ref "R40") (pin "1") (pinfunction "1_1") (pintype "passive"))
    )
    (net (code "39") (name "/SFP+_1_TX_DIS") (class "Default")
      (node (ref "Q2") (pin "1") (pinfunction "G_1") (pintype "passive"))
      (node (ref "R39") (pin "2") (pinfunction "2_2") (pintype "passive"))
    )
    (net (code "40") (name "/SFP+_1_TX_DIS_LS") (class "Default")
      (node (ref "J3") (pin "3") (pinfunction "TX_DISABLE_3") (pintype "input"))
      (node (ref "Q2") (pin "3") (pinfunction "S_3") (pintype "passive"))
      (node (ref "R32") (pin "1") (pinfunction "1_1") (pintype "passive"))
    )
    (net (code "41") (name "/SFP+_1_TX_FAULT") (class "Default")
      (node (ref "J3") (pin "2") (pinfunction "TX_FAULT_2") (pintype "output"))
      (node (ref "R31") (pin "1") (pinfunction "1_1") (pintype "passive"))
    )
    (net (code "42") (name "/SFP+_2_ACT") (class "Default")
      (node (ref "R280") (pin "1") (pinfunction "1_1") (pintype "passive"))
    )
    (net (code "43") (name "/SFP+_2_I2C_SCL") (class "Default")
      (node (ref "J4") (pin "5") (pinfunction "SCL_5") (pintype "input"))
      (node (ref "R45") (pin "1") (pinfunction "1_1") (pintype "passive"))
    )
    (net (code "44") (name "/SFP+_2_I2C_SDA") (class "Default")
      (node (ref "J4") (pin "4") (pinfunction "SDA_4") (pintype "bidirectional"))
      (node (ref "R44") (pin "1") (pinfunction "1_1") (pintype "passive"))
    )
    (net (code "45") (name "/SFP+_2_LOS") (class "Default")
      (node (ref "J4") (pin "8") (pinfunction "LOS_8") (pintype "output"))
      (node (ref "R52") (pin "1") (pinfunction "1_1") (pintype "passive"))
    )
    (net (code "46") (name "/SFP+_2_Link") (class "Default")
      (node (ref "R279") (pin "1") (pinfunction "1_1") (pintype "passive"))
    )
    (net (code "47") (name "/SFP+_2_MOD_ABS") (class "Default")
      (node (ref "J4") (pin "6") (pinfunction "MOD_ABS_6") (pintype "output"))
      (node (ref "R46") (pin "1") (pinfunction "1_1") (pintype "passive"))
    )
    (net (code "48") (name "/SFP+_2_RS0") (class "Default")
      (node (ref "J4") (pin "7") (pinfunction "RS0_7") (pintype "input"))
      (node (ref "R47") (pin "1") (pinfunction "1_1") (pintype "passive"))
      (node (ref "R48") (pin "1") (pinfunction "1_1") (pintype "passive"))
    )
    (net (code "49") (name "/SFP+_2_RS1") (class "Default")
      (node (ref "J4") (pin "9") (pinfunction "RS1_9") (pintype "input"))
      (node (ref "R49") (pin "1") (pinfunction "1_1") (pintype "passive"))
      (node (ref "R51") (pin "1") (pinfunction "1_1") (pintype "passive"))
    )
    (net (code "50") (name "/SFP+_2_TX_DIS") (class "Default")
      (node (ref "Q3") (pin "1") (pinfunction "G_1") (pintype "passive"))
      (node (ref "R50") (pin "2") (pinfunction "2_2") (pintype "passive"))
    )
    (net (code "51") (name "/SFP+_2_TX_DIS_LS") (class "Default")
      (node (ref "J4") (pin "3") (pinfunction "TX_DISABLE_3") (pintype "input"))
      (node (ref "Q3") (pin "3") (pinfunction "S_3") (pintype "passive"))
      (node (ref "R43") (pin "1") (pinfunction "1_1") (pintype "passive"))
    )
    (net (code "52") (name "/SFP+_2_TX_FAULT") (class "Default")
      (node (ref "J4") (pin "2") (pinfunction "TX_FAULT_2") (pintype "output"))
      (node (ref "R42") (pin "1") (pinfunction "1_1") (pintype "passive"))
    )
    (net (code "53") (name "/SFP+_3_ACT") (class "Default")
      (node (ref "R282") (pin "1") (pinfunction "1_1") (pintype "passive"))
    )
    (net (code "54") (name "/SFP+_3_I2C_SCL") (class "Default")
      (node (ref "J5") (pin "5") (pinfunction "SCL_5") (pintype "input"))
      (node (ref "R56") (pin "1") (pinfunction "1_1") (pintype "passive"))
    )
    (net (code "55") (name "/SFP+_3_I2C_SDA") (class "Default")
      (node (ref "J5") (pin "4") (pinfunction "SDA_4") (pintype "bidirectional"))
      (node (ref "R55") (pin "1") (pinfunction "1_1") (pintype "passive"))
    )
    (net (code "56") (name "/SFP+_3_LOS") (class "Default")
      (node (ref "J5") (pin "8") (pinfunction "LOS_8") (pintype "output"))
      (node (ref "R63") (pin "1") (pinfunction "1_1") (pintype "passive"))
    )
    (net (code "57") (name "/SFP+_3_Link") (class "Default")
      (node (ref "R281") (pin "1") (pinfunction "1_1") (pintype "passive"))
    )
    (net (code "58") (name "/SFP+_3_MOD_ABS") (class "Default")
      (node (ref "J5") (pin "6") (pinfunction "MOD_ABS_6") (pintype "output"))
      (node (ref "R57") (pin "1") (pinfunction "1_1") (pintype "passive"))
    )
    (net (code "59") (name "/SFP+_3_RS0") (class "Default")
      (node (ref "J5") (pin "7") (pinfunction "RS0_7") (pintype "input"))
      (node (ref "R58") (pin "1") (pinfunction "1_1") (pintype "passive"))
      (node (ref "R59") (pin "1") (pinfunction "1_1") (pintype "passive"))
    )
    (net (code "60") (name "/SFP+_3_RS1") (class "Default")
      (node (ref "J5") (pin "9") (pinfunction "RS1_9") (pintype "input"))
      (node (ref "R60") (pin "1") (pinfunction "1_1") (pintype "passive"))
      (node (ref "R62") (pin "1") (pinfunction "1_1") (pintype "passive"))
    )
    (net (code "61") (name "/SFP+_3_TX_DIS") (class "Default")
      (node (ref "Q4") (pin "1") (pinfunction "G_1") (pintype "passive"))
      (node (ref "R61") (pin "2") (pinfunction "2_2") (pintype "passive"))
    )
    (net (code "62") (name "/SFP+_3_TX_DIS_LS") (class "Default")
      (node (ref "J5") (pin "3") (pinfunction "TX_DISABLE_3") (pintype "input"))
      (node (ref "Q4") (pin "3") (pinfunction "S_3") (pintype "passive"))
      (node (ref "R54") (pin "1") (pinfunction "1_1") (pintype "passive"))
    )
    (net (code "63") (name "/SFP+_3_TX_FAULT") (class "Default")
      (node (ref "J5") (pin "2") (pinfunction "TX_FAULT_2") (pintype "output"))
      (node (ref "R53") (pin "1") (pinfunction "1_1") (pintype "passive"))
    )
    (net (code "67") (name "GND") (class "Default")
      (node (ref "C100") (pin "2") (pinfunction "2_2") (pintype "passive"))
      (node (ref "C101") (pin "2") (pinfunction "2_2") (pintype "passive"))
      (node (ref "C102") (pin "2") (pinfunction "2_2") (pintype "passive"))
      (node (ref "C87") (pin "2") (pinfunction "2_2") (pintype "passive"))
      (node (ref "C88") (pin "2") (pinfunction "2_2") (pintype "passive"))
      (node (ref "C89") (pin "2") (pinfunction "2_2") (pintype "passive"))
      (node (ref "C90") (pin "2") (pinfunction "2_2") (pintype "passive"))
      (node (ref "C91") (pin "2") (pinfunction "2_2") (pintype "passive"))
      (node (ref "C92") (pin "2") (pinfunction "2_2") (pintype "passive"))
      (node (ref "C93") (pin "2") (pinfunction "2_2") (pintype "passive"))
      (node (ref "C94") (pin "2") (pinfunction "2_2") (pintype "passive"))
      (node (ref "C95") (pin "2") (pinfunction "2_2") (pintype "passive"))
      (node (ref "C96") (pin "2") (pinfunction "2_2") (pintype "passive"))
      (node (ref "C97") (pin "2") (pinfunction "2_2") (pintype "passive"))
      (node (ref "C98") (pin "2") (pinfunction "2_2") (pintype "passive"))
      (node (ref "C99") (pin "2") (pinfunction "2_2") (pintype "passive"))
      (node (ref "D138") (pin "1") (pinfunction "1_1") (pintype "passive"))
      (node (ref "D139") (pin "1") (pinfunction "1_1") (pintype "passive"))
      (node (ref "D140") (pin "1") (pinfunction "1_1") (pintype "passive"))
      (node (ref "D141") (pin "1") (pinfunction "1_1") (pintype "passive"))
      (node (ref "D142") (pin "1") (pinfunction "1_1") (pintype "passive"))
      (node (ref "D143") (pin "1") (pinfunction "1_1") (pintype "passive"))
      (node (ref "D144") (pin "1") (pinfunction "1_1") (pintype "passive"))
      (node (ref "D145") (pin "1") (pinfunction "1_1") (pintype "passive"))
      (node (ref "J2") (pin "1") (pinfunction "VEET_1") (pintype "power_in"))
      (node (ref "J2") (pin "10") (pinfunction "VEER_10") (pintype "power_in"))
      (node (ref "J2") (pin "11") (pinfunction "VEER_11") (pintype "power_in"))
      (node (ref "J2") (pin "14") (pinfunction "VEER_14") (pintype "power_in"))
      (node (ref "J2") (pin "17") (pinfunction "VEET_17") (pintype "power_in"))
      (node (ref "J2") (pin "20") (pinfunction "VEET_20") (pintype "power_in"))
      (node (ref "J3") (pin "1") (pinfunction "VEET_1") (pintype "power_in"))
      (node (ref "J3") (pin "10") (pinfunction "VEER_10") (pintype "power_in"))
      (node (ref "J3") (pin "11") (pinfunction "VEER_11") (pintype "power_in"))
      (node (ref "J3") (pin "14") (pinfunction "VEER_14") (pintype "power_in"))
      (node (ref "J3") (pin "17") (pinfunction "VEET_17") (pintype "power_in"))
      (node (ref "J3") (pin "20") (pinfunction "VEET_20") (pintype "power_in"))
      (node (ref "J4") (pin "1") (pinfunction "VEET_1") (pintype "power_in"))
      (node (ref "J4") (pin "10") (pinfunction "VEER_10") (pintype "power_in"))
      (node (ref "J4") (pin "11") (pinfunction "VEER_11") (pintype "power_in"))
      (node (ref "J4") (pin "14") (pinfunction "VEER_14") (pintype "power_in"))
      (node (ref "J4") (pin "17") (pinfunction "VEET_17") (pintype "power_in"))
      (node (ref "J4") (pin "20") (pinfunction "VEET_20") (pintype "power_in"))
      (node (ref "J5") (pin "1") (pinfunction "VEET_1") (pintype "power_in"))
      (node (ref "J5") (pin "10") (pinfunction "VEER_10") (pintype "power_in"))
      (node (ref "J5") (pin "11") (pinfunction "VEER_11") (pintype "power_in"))
      (node (ref "J5") (pin "14") (pinfunction "VEER_14") (pintype "power_in"))
      (node (ref "J5") (pin "17") (pinfunction "VEET_17") (pintype "power_in"))
      (node (ref "J5") (pin "20") (pinfunction "VEET_20") (pintype "power_in"))
      (node (ref "M1") (pin "MT") (pinfunction "MT_MT") (pintype "passive"))
      (node (ref "M2") (pin "MT") (pinfunction "MT_MT") (pintype "passive"))
      (node (ref "M3") (pin "MT") (pinfunction "MT_MT") (pintype "passive"))
      (node (ref "M4") (pin "MT") (pinfunction "MT_MT") (pintype "passive"))
      (node (ref "Q1") (pin "2") (pinfunction "D_2") (pintype "passive"))
      (node (ref "Q2") (pin "2") (pinfunction "D_2") (pintype "passive"))
      (node (ref "Q3") (pin "2") (pinfunction "D_2") (pintype "passive"))
      (node (ref "Q4") (pin "2") (pinfunction "D_2") (pintype "passive"))
      (node (ref "R26") (pin "2") (pinfunction "2_2") (pintype "passive"))
      (node (ref "R27") (pin "2") (pinfunction "2_2") (pintype "passive"))
      (node (ref "R28") (pin "1") (pinfunction "1_1") (pintype "passive"))
      (node (ref "R37") (pin "2") (pinfunction "2_2") (pintype "passive"))
      (node (ref "R38") (pin "2") (pinfunction "2_2") (pintype "passive"))
      (node (ref "R39") (pin "1") (pinfunction "1_1") (pintype "passive"))
      (node (ref "R48") (pin "2") (pinfunction "2_2") (pintype "passive"))
      (node (ref "R49") (pin "2") (pinfunction "2_2") (pintype "passive"))
      (node (ref "R50") (pin "1") (pinfunction "1_1") (pintype "passive"))
      (node (ref "R59") (pin "2") (pinfunction "2_2") (pintype "passive"))
      (node (ref "R60") (pin "2") (pinfunction "2_2") (pintype "passive"))
      (node (ref "R61") (pin "1") (pinfunction "1_1") (pintype "passive"))
    )
    (net (code "68") (name "Net-(D138-Pad2)") (class "Default")
      (node (ref "D138") (pin "2") (pinfunction "2_2") (pintype "passive"))
      (node (ref "R275") (pin "2") (pinfunction "2_2") (pintype "passive"))
    )
    (net (code "69") (name "Net-(D139-Pad2)") (class "Default")
      (node (ref "D139") (pin "2") (pinfunction "2_2") (pintype "passive"))
      (node (ref "R276") (pin "2") (pinfunction "2_2") (pintype "passive"))
    )
    (net (code "70") (name "Net-(D140-Pad2)") (class "Default")
      (node (ref "D140") (pin "2") (pinfunction "2_2") (pintype "passive"))
      (node (ref "R277") (pin "2") (pinfunction "2_2") (pintype "passive"))
    )
    (net (code "71") (name "Net-(D141-Pad2)") (class "Default")
      (node (ref "D141") (pin "2") (pinfunction "2_2") (pintype "passive"))
      (node (ref "R278") (pin "2") (pinfunction "2_2") (pintype "passive"))
    )
    (net (code "72") (name "Net-(D142-Pad2)") (class "Default")
      (node (ref "D142") (pin "2") (pinfunction "2_2") (pintype "passive"))
      (node (ref "R279") (pin "2") (pinfunction "2_2") (pintype "passive"))
    )
    (net (code "73") (name "Net-(D143-Pad2)") (class "Default")
      (node (ref "D143") (pin "2") (pinfunction "2_2") (pintype "passive"))
      (node (ref "R280") (pin "2") (pinfunction "2_2") (pintype "passive"))
    )
    (net (code "74") (name "Net-(D144-Pad2)") (class "Default")
      (node (ref "D144") (pin "2") (pinfunction "2_2") (pintype "passive"))
      (node (ref "R281") (pin "2") (pinfunction "2_2") (pintype "passive"))
    )
    (net (code "75") (name "Net-(D145-Pad2)") (class "Default")
      (node (ref "D145") (pin "2") (pinfunction "2_2") (pintype "passive"))
      (node (ref "R282") (pin "2") (pinfunction "2_2") (pintype "passive"))
    )
    (net (code "76") (name "Net-(J2-VCCR)") (class "Default")
      (node (ref "C87") (pin "1") (pinfunction "1_1") (pintype "passive"))
      (node (ref "C88") (pin "1") (pinfunction "1_1") (pintype "passive"))
      (node (ref "J2") (pin "15") (pinfunction "VCCR_15") (pintype "power_in"))
      (node (ref "L1") (pin "2") (pinfunction "2_2") (pintype "passive"))
    )
    (net (code "77") (name "Net-(J2-VCCT)") (class "Default")
      (node (ref "C89") (pin "1") (pinfunction "1_1") (pintype "passive"))
      (node (ref "C90") (pin "1") (pinfunction "1_1") (pintype "passive"))
      (node (ref "J2") (pin "16") (pinfunction "VCCT_16") (pintype "power_in"))
      (node (ref "L2") (pin "2") (pinfunction "2_2") (pintype "passive"))
    )
    (net (code "78") (name "Net-(J3-VCCR)") (class "Default")
      (node (ref "C91") (pin "1") (pinfunction "1_1") (pintype "passive"))
      (node (ref "C92") (pin "1") (pinfunction "1_1") (pintype "passive"))
      (node (ref "J3") (pin "15") (pinfunction "VCCR_15") (pintype "power_in"))
      (node (ref "L3") (pin "2") (pinfunction "2_2") (pintype "passive"))
    )
    (net (code "79") (name "Net-(J3-VCCT)") (class "Default")
      (node (ref "C93") (pin "1") (pinfunction "1_1") (pintype "passive"))
      (node (ref "C94") (pin "1") (pinfunction "1_1") (pintype "passive"))
      (node (ref "J3") (pin "16") (pinfunction "VCCT_16") (pintype "power_in"))
      (node (ref "L4") (pin "2") (pinfunction "2_2") (pintype "passive"))
    )
    (net (code "80") (name "Net-(J4-VCCR)") (class "Default")
      (node (ref "C95") (pin "1") (pinfunction "1_1") (pintype "passive"))
      (node (ref "C96") (pin "1") (pinfunction "1_1") (pintype "passive"))
      (node (ref "J4") (pin "15") (pinfunction "VCCR_15") (pintype "power_in"))
      (node (ref "L5") (pin "2") (pinfunction "2_2") (pintype "passive"))
    )
    (net (code "81") (name "Net-(J4-VCCT)") (class "Default")
      (node (ref "C97") (pin "1") (pinfunction "1_1") (pintype "passive"))
      (node (ref "C98") (pin "1") (pinfunction "1_1") (pintype "passive"))
      (node (ref "J4") (pin "16") (pinfunction "VCCT_16") (pintype "power_in"))
      (node (ref "L6") (pin "2") (pinfunction "2_2") (pintype "passive"))
    )
    (net (code "82") (name "Net-(J5-VCCR)") (class "Default")
      (node (ref "C100") (pin "1") (pinfunction "1_1") (pintype "passive"))
      (node (ref "C99") (pin "1") (pinfunction "1_1") (pintype "passive"))
      (node (ref "J5") (pin "15") (pinfunction "VCCR_15") (pintype "power_in"))
      (node (ref "L7") (pin "2") (pinfunction "2_2") (pintype "passive"))
    )
    (net (code "83") (name "Net-(J5-VCCT)") (class "Default")
      (node (ref "C101") (pin "1") (pinfunction "1_1") (pintype "passive"))
      (node (ref "C102") (pin "1") (pinfunction "1_1") (pintype "passive"))
      (node (ref "J5") (pin "16") (pinfunction "VCCT_16") (pintype "power_in"))
      (node (ref "L8") (pin "2") (pinfunction "2_2") (pintype "passive"))
    )
    (net (code "84") (name "VCC3V3") (class "Default")
      (node (ref "L1") (pin "1") (pinfunction "1_1") (pintype "passive"))
      (node (ref "L2") (pin "1") (pinfunction "1_1") (pintype "passive"))
      (node (ref "L3") (pin "1") (pinfunction "1_1") (pintype "passive"))
      (node (ref "L4") (pin "1") (pinfunction "1_1") (pintype "passive"))
      (node (ref "L5") (pin "1") (pinfunction "1_1") (pintype "passive"))
      (node (ref "L6") (pin "1") (pinfunction "1_1") (pintype "passive"))
      (node (ref "L7") (pin "1") (pinfunction "1_1") (pintype "passive"))
      (node (ref "L8") (pin "1") (pinfunction "1_1") (pintype "passive"))
      (node (ref "R20") (pin "2") (pinfunction "2_2") (pintype "passive"))
      (node (ref "R21") (pin "2") (pinfunction "2_2") (pintype "passive"))
      (node (ref "R22") (pin "2") (pinfunction "2_2") (pintype "passive"))
      (node (ref "R23") (pin "2") (pinfunction "2_2") (pintype "passive"))
      (node (ref "R24") (pin "2") (pinfunction "2_2") (pintype "passive"))
      (node (ref "R25") (pin "2") (pinfunction "2_2") (pintype "passive"))
      (node (ref "R29") (pin "2") (pinfunction "2_2") (pintype "passive"))
      (node (ref "R30") (pin "2") (pinfunction "2_2") (pintype "passive"))
      (node (ref "R31") (pin "2") (pinfunction "2_2") (pintype "passive"))
      (node (ref "R32") (pin "2") (pinfunction "2_2") (pintype "passive"))
      (node (ref "R33") (pin "2") (pinfunction "2_2") (pintype "passive"))
      (node (ref "R34") (pin "2") (pinfunction "2_2") (pintype "passive"))
      (node (ref "R35") (pin "2") (pinfunction "2_2") (pintype "passive"))
      (node (ref "R36") (pin "2") (pinfunction "2_2") (pintype "passive"))
      (node (ref "R40") (pin "2") (pinfunction "2_2") (pintype "passive"))
      (node (ref "R41") (pin "2") (pinfunction "2_2") (pintype "passive"))
      (node (ref "R42") (pin "2") (pinfunction "2_2") (pintype "passive"))
      (node (ref "R43") (pin "2") (pinfunction "2_2") (pintype "passive"))
      (node (ref "R44") (pin "2") (pinfunction "2_2") (pintype "passive"))
      (node (ref "R45") (pin "2") (pinfunction "2_2") (pintype "passive"))
      (node (ref "R46") (pin "2") (pinfunction "2_2") (pintype "passive"))
      (node (ref "R47") (pin "2") (pinfunction "2_2") (pintype "passive"))
      (node (ref "R51") (pin "2") (pinfunction "2_2") (pintype "passive"))
      (node (ref "R52") (pin "2") (pinfunction "2_2") (pintype "passive"))
      (node (ref "R53") (pin "2") (pinfunction "2_2") (pintype "passive"))
      (node (ref "R54") (pin "2") (pinfunction "2_2") (pintype "passive"))
      (node (ref "R55") (pin "2") (pinfunction "2_2") (pintype "passive"))
      (node (ref "R56") (pin "2") (pinfunction "2_2") (pintype "passive"))
      (node (ref "R57") (pin "2") (pinfunction "2_2") (pintype "passive"))
      (node (ref "R58") (pin "2") (pinfunction "2_2") (pintype "passive"))
      (node (ref "R62") (pin "2") (pinfunction "2_2") (pintype "passive"))
      (node (ref "R63") (pin "2") (pinfunction "2_2") (pintype "passive"))
    )
  )
)
